# OutputStage.net
KiCad netlist of a schematic drawn in Altium Designer
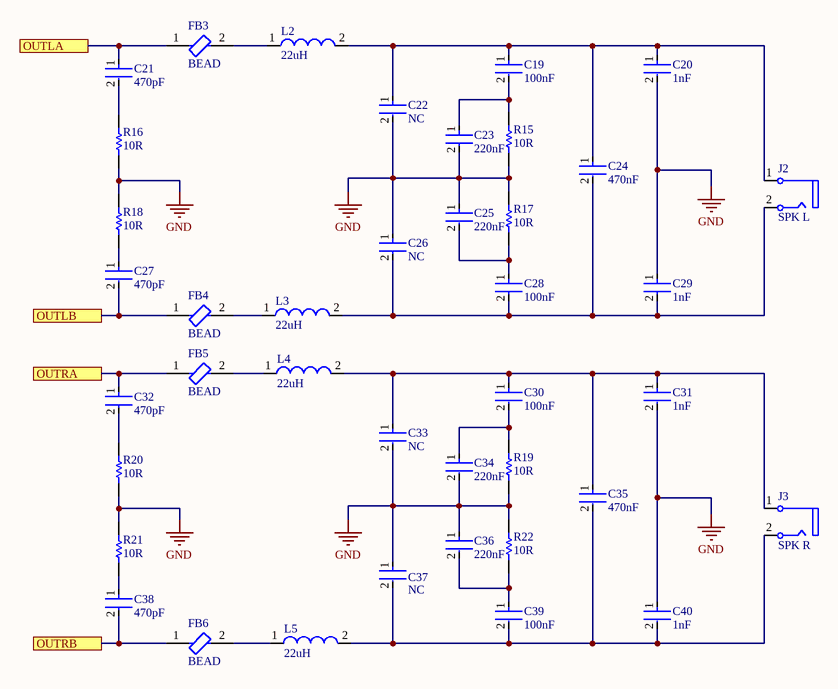
[diagram p0: OutputStage.SchDoc]

(export (version "E")
  (design (tool "Eeschema 10.0.6"))
  (components
    (comp (ref "C19")
      (value "100nF")
      (footprint "FP-CC0805-0_85-MFG")
      (description "CC0805 220 nF X7R 10.00% 50 V")
      (fields (field (name "TOLERANCE") "0.1"))
      (libsource (lib "Altium Content Vault") (part "11868f565c42a9108669ba33697ecf6"))
    )
    (comp (ref "C20")
      (value "1nF")
      (footprint "FP-CC0603-DA-MFG")
      (description "CAP CER 10000PF 50V X7R 0603")
      (fields (field (name "TOLERANCE") "0.1") (field (name "MANUFACTURER PART NUMBER") "CC0603KRX7R9BB103"))
      (libsource (lib "Altium Content Vault") (part "11868f565c42a9108669ba33697ecf6"))
    )
    (comp (ref "C21")
      (value "470pF")
      (footprint "FP-CC0603-DA-MFG")
      (description "CAP CER 10000PF 50V X7R 0603")
      (fields (field (name "TOLERANCE") "0.1") (field (name "MANUFACTURER PART NUMBER") "CC0603KRX7R9BB103"))
      (libsource (lib "Altium Content Vault") (part "11868f565c42a9108669ba33697ecf6"))
    )
    (comp (ref "C22")
      (value "NC")
      (footprint "FP-CL31-IPC_C")
      (description "Cap Ceramic 1nF 2kV X7R ±20% SMD 1206 +125°C Embossed T/R")
      (fields (field (name "TOLERANCE") "20%"))
      (libsource (lib "Altium Content Vault") (part "b4654b650e69147ec39a6b967a45e02"))
    )
    (comp (ref "C23")
      (value "220nF")
      (footprint "FP-CC0805-0_85-MFG")
      (description "CC0805 220 nF X7R 10.00% 50 V")
      (fields (field (name "TOLERANCE") "0.1"))
      (libsource (lib "Altium Content Vault") (part "11868f565c42a9108669ba33697ecf6"))
    )
    (comp (ref "C24")
      (value "470nF")
      (footprint "FP-CC0603-DA-MFG")
      (description "CAP CER 10000PF 50V X7R 0603")
      (fields (field (name "TOLERANCE") "0.1") (field (name "MANUFACTURER PART NUMBER") "CC0603KRX7R9BB103"))
      (libsource (lib "Altium Content Vault") (part "11868f565c42a9108669ba33697ecf6"))
    )
    (comp (ref "C25")
      (value "220nF")
      (footprint "FP-CC0805-0_85-MFG")
      (description "CC0805 220 nF X7R 10.00% 50 V")
      (fields (field (name "TOLERANCE") "0.1"))
      (libsource (lib "Altium Content Vault") (part "11868f565c42a9108669ba33697ecf6"))
    )
    (comp (ref "C26")
      (value "NC")
      (footprint "FP-CL31-IPC_C")
      (description "Cap Ceramic 1nF 2kV X7R ±20% SMD 1206 +125°C Embossed T/R")
      (fields (field (name "TOLERANCE") "20%"))
      (libsource (lib "Altium Content Vault") (part "b4654b650e69147ec39a6b967a45e02"))
    )
    (comp (ref "C27")
      (value "470pF")
      (footprint "FP-CC0603-DA-MFG")
      (description "CAP CER 10000PF 50V X7R 0603")
      (fields (field (name "TOLERANCE") "0.1") (field (name "MANUFACTURER PART NUMBER") "CC0603KRX7R9BB103"))
      (libsource (lib "Altium Content Vault") (part "11868f565c42a9108669ba33697ecf6"))
    )
    (comp (ref "C28")
      (value "100nF")
      (footprint "FP-CC0805-0_85-MFG")
      (description "CC0805 220 nF X7R 10.00% 50 V")
      (fields (field (name "TOLERANCE") "0.1"))
      (libsource (lib "Altium Content Vault") (part "11868f565c42a9108669ba33697ecf6"))
    )
    (comp (ref "C29")
      (value "1nF")
      (footprint "FP-CC0603-DA-MFG")
      (description "CAP CER 10000PF 50V X7R 0603")
      (fields (field (name "TOLERANCE") "0.1") (field (name "MANUFACTURER PART NUMBER") "CC0603KRX7R9BB103"))
      (libsource (lib "Altium Content Vault") (part "11868f565c42a9108669ba33697ecf6"))
    )
    (comp (ref "C30")
      (value "100nF")
      (footprint "FP-CC0805-0_85-MFG")
      (description "CC0805 220 nF X7R 10.00% 50 V")
      (fields (field (name "TOLERANCE") "0.1"))
      (libsource (lib "Altium Content Vault") (part "11868f565c42a9108669ba33697ecf6"))
    )
    (comp (ref "C31")
      (value "1nF")
      (footprint "FP-CC0603-DA-MFG")
      (description "CAP CER 10000PF 50V X7R 0603")
      (fields (field (name "TOLERANCE") "0.1") (field (name "MANUFACTURER PART NUMBER") "CC0603KRX7R9BB103"))
      (libsource (lib "Altium Content Vault") (part "11868f565c42a9108669ba33697ecf6"))
    )
    (comp (ref "C32")
      (value "470pF")
      (footprint "FP-CC0603-DA-MFG")
      (description "CAP CER 10000PF 50V X7R 0603")
      (fields (field (name "TOLERANCE") "0.1") (field (name "MANUFACTURER PART NUMBER") "CC0603KRX7R9BB103"))
      (libsource (lib "Altium Content Vault") (part "11868f565c42a9108669ba33697ecf6"))
    )
    (comp (ref "C33")
      (value "NC")
      (footprint "FP-CL31-IPC_C")
      (description "Cap Ceramic 1nF 2kV X7R ±20% SMD 1206 +125°C Embossed T/R")
      (fields (field (name "TOLERANCE") "20%"))
      (libsource (lib "Altium Content Vault") (part "b4654b650e69147ec39a6b967a45e02"))
    )
    (comp (ref "C34")
      (value "220nF")
      (footprint "FP-CC0805-0_85-MFG")
      (description "CC0805 220 nF X7R 10.00% 50 V")
      (fields (field (name "TOLERANCE") "0.1"))
      (libsource (lib "Altium Content Vault") (part "11868f565c42a9108669ba33697ecf6"))
    )
    (comp (ref "C35")
      (value "470nF")
      (footprint "FP-CC0603-DA-MFG")
      (description "CAP CER 10000PF 50V X7R 0603")
      (fields (field (name "TOLERANCE") "0.1") (field (name "MANUFACTURER PART NUMBER") "CC0603KRX7R9BB103"))
      (libsource (lib "Altium Content Vault") (part "11868f565c42a9108669ba33697ecf6"))
    )
    (comp (ref "C36")
      (value "220nF")
      (footprint "FP-CC0805-0_85-MFG")
      (description "CC0805 220 nF X7R 10.00% 50 V")
      (fields (field (name "TOLERANCE") "0.1"))
      (libsource (lib "Altium Content Vault") (part "11868f565c42a9108669ba33697ecf6"))
    )
    (comp (ref "C37")
      (value "NC")
      (footprint "FP-CL31-IPC_C")
      (description "Cap Ceramic 1nF 2kV X7R ±20% SMD 1206 +125°C Embossed T/R")
      (fields (field (name "TOLERANCE") "20%"))
      (libsource (lib "Altium Content Vault") (part "b4654b650e69147ec39a6b967a45e02"))
    )
    (comp (ref "C38")
      (value "470pF")
      (footprint "FP-CC0603-DA-MFG")
      (description "CAP CER 10000PF 50V X7R 0603")
      (fields (field (name "TOLERANCE") "0.1") (field (name "MANUFACTURER PART NUMBER") "CC0603KRX7R9BB103"))
      (libsource (lib "Altium Content Vault") (part "11868f565c42a9108669ba33697ecf6"))
    )
    (comp (ref "C39")
      (value "100nF")
      (footprint "FP-CC0805-0_85-MFG")
      (description "CC0805 220 nF X7R 10.00% 50 V")
      (fields (field (name "TOLERANCE") "0.1"))
      (libsource (lib "Altium Content Vault") (part "11868f565c42a9108669ba33697ecf6"))
    )
    (comp (ref "C40")
      (value "1nF")
      (footprint "FP-CC0603-DA-MFG")
      (description "CAP CER 10000PF 50V X7R 0603")
      (fields (field (name "TOLERANCE") "0.1") (field (name "MANUFACTURER PART NUMBER") "CC0603KRX7R9BB103"))
      (libsource (lib "Altium Content Vault") (part "11868f565c42a9108669ba33697ecf6"))
    )
    (comp (ref "FB3")
      (value "BEAD")
      (footprint "FP-BLM18-0_15-t0_8-IPC_B")
      (description "Chip Ferrite Bead, 0603, 75Ω @ 100MHz, 0.3Ω, 25%, 600mA")
      (fields (field (name "TOLERANCE") "25%"))
      (libsource (lib "Altium Content Vault") (part "5f30dd21d616792df468990f7003faa"))
    )
    (comp (ref "FB4")
      (value "BEAD")
      (footprint "FP-BLM18-0_15-t0_8-IPC_B")
      (description "Chip Ferrite Bead, 0603, 75Ω @ 100MHz, 0.3Ω, 25%, 600mA")
      (fields (field (name "TOLERANCE") "25%"))
      (libsource (lib "Altium Content Vault") (part "5f30dd21d616792df468990f7003faa"))
    )
    (comp (ref "FB5")
      (value "BEAD")
      (footprint "FP-BLM18-0_15-t0_8-IPC_B")
      (description "Chip Ferrite Bead, 0603, 75Ω @ 100MHz, 0.3Ω, 25%, 600mA")
      (fields (field (name "TOLERANCE") "25%"))
      (libsource (lib "Altium Content Vault") (part "5f30dd21d616792df468990f7003faa"))
    )
    (comp (ref "FB6")
      (value "BEAD")
      (footprint "FP-BLM18-0_15-t0_8-IPC_B")
      (description "Chip Ferrite Bead, 0603, 75Ω @ 100MHz, 0.3Ω, 25%, 600mA")
      (fields (field (name "TOLERANCE") "25%"))
      (libsource (lib "Altium Content Vault") (part "5f30dd21d616792df468990f7003faa"))
    )
    (comp (ref "J2")
      (value "SPK L")
      (footprint "CUI-RCJ-041_V")
      (description "Female RCJ Jack, 2 Position, Height 11.724 mm, Tail Length 4 mm, RoHS, Bulk")
      (libsource (lib "Altium Content Vault") (part "JACK-2CD2"))
    )
    (comp (ref "J3")
      (value "SPK R")
      (footprint "CUI-RCJ-041_V")
      (description "Female RCJ Jack, 2 Position, Height 11.724 mm, Tail Length 4 mm, RoHS, Bulk")
      (libsource (lib "Altium Content Vault") (part "JACK-2CD2"))
    )
    (comp (ref "L2")
      (value "22uH")
      (footprint "WE-PD-XXL")
      (description "SMD-Shielded Power Inductor WE-PD, L = 22.0 µH")
      (libsource (lib "Altium Content Vault") (part "PAS-IND-INDUCTOR-2"))
    )
    (comp (ref "L3")
      (value "22uH")
      (footprint "WE-PD-XXL")
      (description "SMD-Shielded Power Inductor WE-PD, L = 22.0 µH")
      (libsource (lib "Altium Content Vault") (part "PAS-IND-INDUCTOR-2"))
    )
    (comp (ref "L4")
      (value "22uH")
      (footprint "WE-PD-XXL")
      (description "SMD-Shielded Power Inductor WE-PD, L = 22.0 µH")
      (libsource (lib "Altium Content Vault") (part "PAS-IND-INDUCTOR-2"))
    )
    (comp (ref "L5")
      (value "22uH")
      (footprint "WE-PD-XXL")
      (description "SMD-Shielded Power Inductor WE-PD, L = 22.0 µH")
      (libsource (lib "Altium Content Vault") (part "PAS-IND-INDUCTOR-2"))
    )
    (comp (ref "R15")
      (value "10R")
      (footprint "RESC3116X65X40NL10T20")
      (fields (field (name "PART NUMBER") "RC1206JR-07100ML") (field (name "MANUFACTURER") "Yageo"))
      (libsource (lib "Altium Content Vault") (part "RES"))
    )
    (comp (ref "R16")
      (value "10R")
      (footprint "RESC1608X55X25ML10T15")
      (description "Chip Resistor, 100 Ohm, +/- 5%, 50 V, 0603 (1608 Metric), RoHS, Tape and Reel")
      (fields (field (name "MANUFACTURER") "Yageo") (field (name "TOLERANCE") "5%"))
      (libsource (lib "Altium Content Vault") (part "RES-2"))
    )
    (comp (ref "R17")
      (value "10R")
      (footprint "RESC3116X65X40NL10T20")
      (fields (field (name "PART NUMBER") "RC1206JR-07100ML") (field (name "MANUFACTURER") "Yageo"))
      (libsource (lib "Altium Content Vault") (part "RES"))
    )
    (comp (ref "R18")
      (value "10R")
      (footprint "RESC1608X55X25ML10T15")
      (description "Chip Resistor, 100 Ohm, +/- 5%, 50 V, 0603 (1608 Metric), RoHS, Tape and Reel")
      (fields (field (name "MANUFACTURER") "Yageo") (field (name "TOLERANCE") "5%"))
      (libsource (lib "Altium Content Vault") (part "RES-2"))
    )
    (comp (ref "R19")
      (value "10R")
      (footprint "RESC3116X65X40NL10T20")
      (fields (field (name "PART NUMBER") "RC1206JR-07100ML") (field (name "MANUFACTURER") "Yageo"))
      (libsource (lib "Altium Content Vault") (part "RES"))
    )
    (comp (ref "R20")
      (value "10R")
      (footprint "RESC1608X55X25ML10T15")
      (description "Chip Resistor, 100 Ohm, +/- 5%, 50 V, 0603 (1608 Metric), RoHS, Tape and Reel")
      (fields (field (name "MANUFACTURER") "Yageo") (field (name "TOLERANCE") "5%"))
      (libsource (lib "Altium Content Vault") (part "RES-2"))
    )
    (comp (ref "R21")
      (value "10R")
      (footprint "RESC1608X55X25ML10T15")
      (description "Chip Resistor, 100 Ohm, +/- 5%, 50 V, 0603 (1608 Metric), RoHS, Tape and Reel")
      (fields (field (name "MANUFACTURER") "Yageo") (field (name "TOLERANCE") "5%"))
      (libsource (lib "Altium Content Vault") (part "RES-2"))
    )
    (comp (ref "R22")
      (value "10R")
      (footprint "RESC3116X65X40NL10T20")
      (fields (field (name "PART NUMBER") "RC1206JR-07100ML") (field (name "MANUFACTURER") "Yageo"))
      (libsource (lib "Altium Content Vault") (part "RES"))
    )
  )
  (nets
    (net (code "1") (name "/OUTLA") (class "Default")
      (node (ref "C21") (pin "1") (pinfunction "1_1") (pintype "passive"))
      (node (ref "FB3") (pin "1") (pinfunction "1_1") (pintype "passive"))
    )
    (net (code "2") (name "/OUTLB") (class "Default")
      (node (ref "C27") (pin "2") (pinfunction "2_2") (pintype "passive"))
      (node (ref "FB4") (pin "1") (pinfunction "1_1") (pintype "passive"))
    )
    (net (code "3") (name "/OUTRA") (class "Default")
      (node (ref "C32") (pin "1") (pinfunction "1_1") (pintype "passive"))
      (node (ref "FB5") (pin "1") (pinfunction "1_1") (pintype "passive"))
    )
    (net (code "4") (name "/OUTRB") (class "Default")
      (node (ref "C38") (pin "2") (pinfunction "2_2") (pintype "passive"))
      (node (ref "FB6") (pin "1") (pinfunction "1_1") (pintype "passive"))
    )
    (net (code "5") (name "GND") (class "Default")
      (node (ref "C20") (pin "2") (pinfunction "2_2") (pintype "passive"))
      (node (ref "C22") (pin "2") (pinfunction "2_2") (pintype "passive"))
      (node (ref "C23") (pin "2") (pinfunction "2_2") (pintype "passive"))
      (node (ref "C25") (pin "1") (pinfunction "1_1") (pintype "passive"))
      (node (ref "C26") (pin "1") (pinfunction "1_1") (pintype "passive"))
      (node (ref "C29") (pin "1") (pinfunction "1_1") (pintype "passive"))
      (node (ref "C31") (pin "2") (pinfunction "2_2") (pintype "passive"))
      (node (ref "C33") (pin "2") (pinfunction "2_2") (pintype "passive"))
      (node (ref "C34") (pin "2") (pinfunction "2_2") (pintype "passive"))
      (node (ref "C36") (pin "1") (pinfunction "1_1") (pintype "passive"))
      (node (ref "C37") (pin "1") (pinfunction "1_1") (pintype "passive"))
      (node (ref "C40") (pin "1") (pinfunction "1_1") (pintype "passive"))
      (node (ref "R15") (pin "1") (pinfunction "1_1") (pintype "passive"))
      (node (ref "R16") (pin "1") (pinfunction "1_1") (pintype "passive"))
      (node (ref "R17") (pin "2") (pinfunction "2_2") (pintype "passive"))
      (node (ref "R18") (pin "2") (pinfunction "2_2") (pintype "passive"))
      (node (ref "R19") (pin "1") (pinfunction "1_1") (pintype "passive"))
      (node (ref "R20") (pin "1") (pinfunction "1_1") (pintype "passive"))
      (node (ref "R21") (pin "2") (pinfunction "2_2") (pintype "passive"))
      (node (ref "R22") (pin "2") (pinfunction "2_2") (pintype "passive"))
    )
    (net (code "6") (name "Net-(C19-Pad1)") (class "Default")
      (node (ref "C19") (pin "1") (pinfunction "1_1") (pintype "passive"))
      (node (ref "C20") (pin "1") (pinfunction "1_1") (pintype "passive"))
      (node (ref "C22") (pin "1") (pinfunction "1_1") (pintype "passive"))
      (node (ref "C24") (pin "1") (pinfunction "1_1") (pintype "passive"))
      (node (ref "J2") (pin "1") (pinfunction "1_1") (pintype "passive"))
      (node (ref "L2") (pin "2") (pinfunction "2_2") (pintype "passive"))
    )
    (net (code "7") (name "Net-(C19-Pad2)") (class "Default")
      (node (ref "C19") (pin "2") (pinfunction "2_2") (pintype "passive"))
      (node (ref "C23") (pin "1") (pinfunction "1_1") (pintype "passive"))
      (node (ref "R15") (pin "2") (pinfunction "2_2") (pintype "passive"))
    )
    (net (code "8") (name "Net-(C21-Pad2)") (class "Default")
      (node (ref "C21") (pin "2") (pinfunction "2_2") (pintype "passive"))
      (node (ref "R16") (pin "2") (pinfunction "2_2") (pintype "passive"))
    )
    (net (code "9") (name "Net-(C24-Pad2)") (class "Default")
      (node (ref "C24") (pin "2") (pinfunction "2_2") (pintype "passive"))
      (node (ref "C26") (pin "2") (pinfunction "2_2") (pintype "passive"))
      (node (ref "C28") (pin "2") (pinfunction "2_2") (pintype "passive"))
      (node (ref "C29") (pin "2") (pinfunction "2_2") (pintype "passive"))
      (node (ref "J2") (pin "2") (pinfunction "2_2") (pintype "passive"))
      (node (ref "L3") (pin "2") (pinfunction "2_2") (pintype "passive"))
    )
    (net (code "10") (name "Net-(C25-Pad2)") (class "Default")
      (node (ref "C25") (pin "2") (pinfunction "2_2") (pintype "passive"))
      (node (ref "C28") (pin "1") (pinfunction "1_1") (pintype "passive"))
      (node (ref "R17") (pin "1") (pinfunction "1_1") (pintype "passive"))
    )
    (net (code "11") (name "Net-(C27-Pad1)") (class "Default")
      (node (ref "C27") (pin "1") (pinfunction "1_1") (pintype "passive"))
      (node (ref "R18") (pin "1") (pinfunction "1_1") (pintype "passive"))
    )
    (net (code "12") (name "Net-(C30-Pad1)") (class "Default")
      (node (ref "C30") (pin "1") (pinfunction "1_1") (pintype "passive"))
      (node (ref "C31") (pin "1") (pinfunction "1_1") (pintype "passive"))
      (node (ref "C33") (pin "1") (pinfunction "1_1") (pintype "passive"))
      (node (ref "C35") (pin "1") (pinfunction "1_1") (pintype "passive"))
      (node (ref "J3") (pin "1") (pinfunction "1_1") (pintype "passive"))
      (node (ref "L4") (pin "2") (pinfunction "2_2") (pintype "passive"))
    )
    (net (code "13") (name "Net-(C30-Pad2)") (class "Default")
      (node (ref "C30") (pin "2") (pinfunction "2_2") (pintype "passive"))
      (node (ref "C34") (pin "1") (pinfunction "1_1") (pintype "passive"))
      (node (ref "R19") (pin "2") (pinfunction "2_2") (pintype "passive"))
    )
    (net (code "14") (name "Net-(C32-Pad2)") (class "Default")
      (node (ref "C32") (pin "2") (pinfunction "2_2") (pintype "passive"))
      (node (ref "R20") (pin "2") (pinfunction "2_2") (pintype "passive"))
    )
    (net (code "15") (name "Net-(C35-Pad2)") (class "Default")
      (node (ref "C35") (pin "2") (pinfunction "2_2") (pintype "passive"))
      (node (ref "C37") (pin "2") (pinfunction "2_2") (pintype "passive"))
      (node (ref "C39") (pin "2") (pinfunction "2_2") (pintype "passive"))
      (node (ref "C40") (pin "2") (pinfunction "2_2") (pintype "passive"))
      (node (ref "J3") (pin "2") (pinfunction "2_2") (pintype "passive"))
      (node (ref "L5") (pin "2") (pinfunction "2_2") (pintype "passive"))
    )
    (net (code "16") (name "Net-(C36-Pad2)") (class "Default")
      (node (ref "C36") (pin "2") (pinfunction "2_2") (pintype "passive"))
      (node (ref "C39") (pin "1") (pinfunction "1_1") (pintype "passive"))
      (node (ref "R22") (pin "1") (pinfunction "1_1") (pintype "passive"))
    )
    (net (code "17") (name "Net-(C38-Pad1)") (class "Default")
      (node (ref "C38") (pin "1") (pinfunction "1_1") (pintype "passive"))
      (node (ref "R21") (pin "1") (pinfunction "1_1") (pintype "passive"))
    )
    (net (code "18") (name "Net-(FB3-Pad2)") (class "Default")
      (node (ref "FB3") (pin "2") (pinfunction "2_2") (pintype "passive"))
      (node (ref "L2") (pin "1") (pinfunction "1_1") (pintype "passive"))
    )
    (net (code "19") (name "Net-(FB4-Pad2)") (class "Default")
      (node (ref "FB4") (pin "2") (pinfunction "2_2") (pintype "passive"))
      (node (ref "L3") (pin "1") (pinfunction "1_1") (pintype "passive"))
    )
    (net (code "20") (name "Net-(FB5-Pad2)") (class "Default")
      (node (ref "FB5") (pin "2") (pinfunction "2_2") (pintype "passive"))
      (node (ref "L4") (pin "1") (pinfunction "1_1") (pintype "passive"))
    )
    (net (code "21") (name "Net-(FB6-Pad2)") (class "Default")
      (node (ref "FB6") (pin "2") (pinfunction "2_2") (pintype "passive"))
      (node (ref "L5") (pin "1") (pinfunction "1_1") (pintype "passive"))
    )
  )
)
